# 02_PWR_IN.net
KiCad netlist of a schematic drawn in Altium Designer
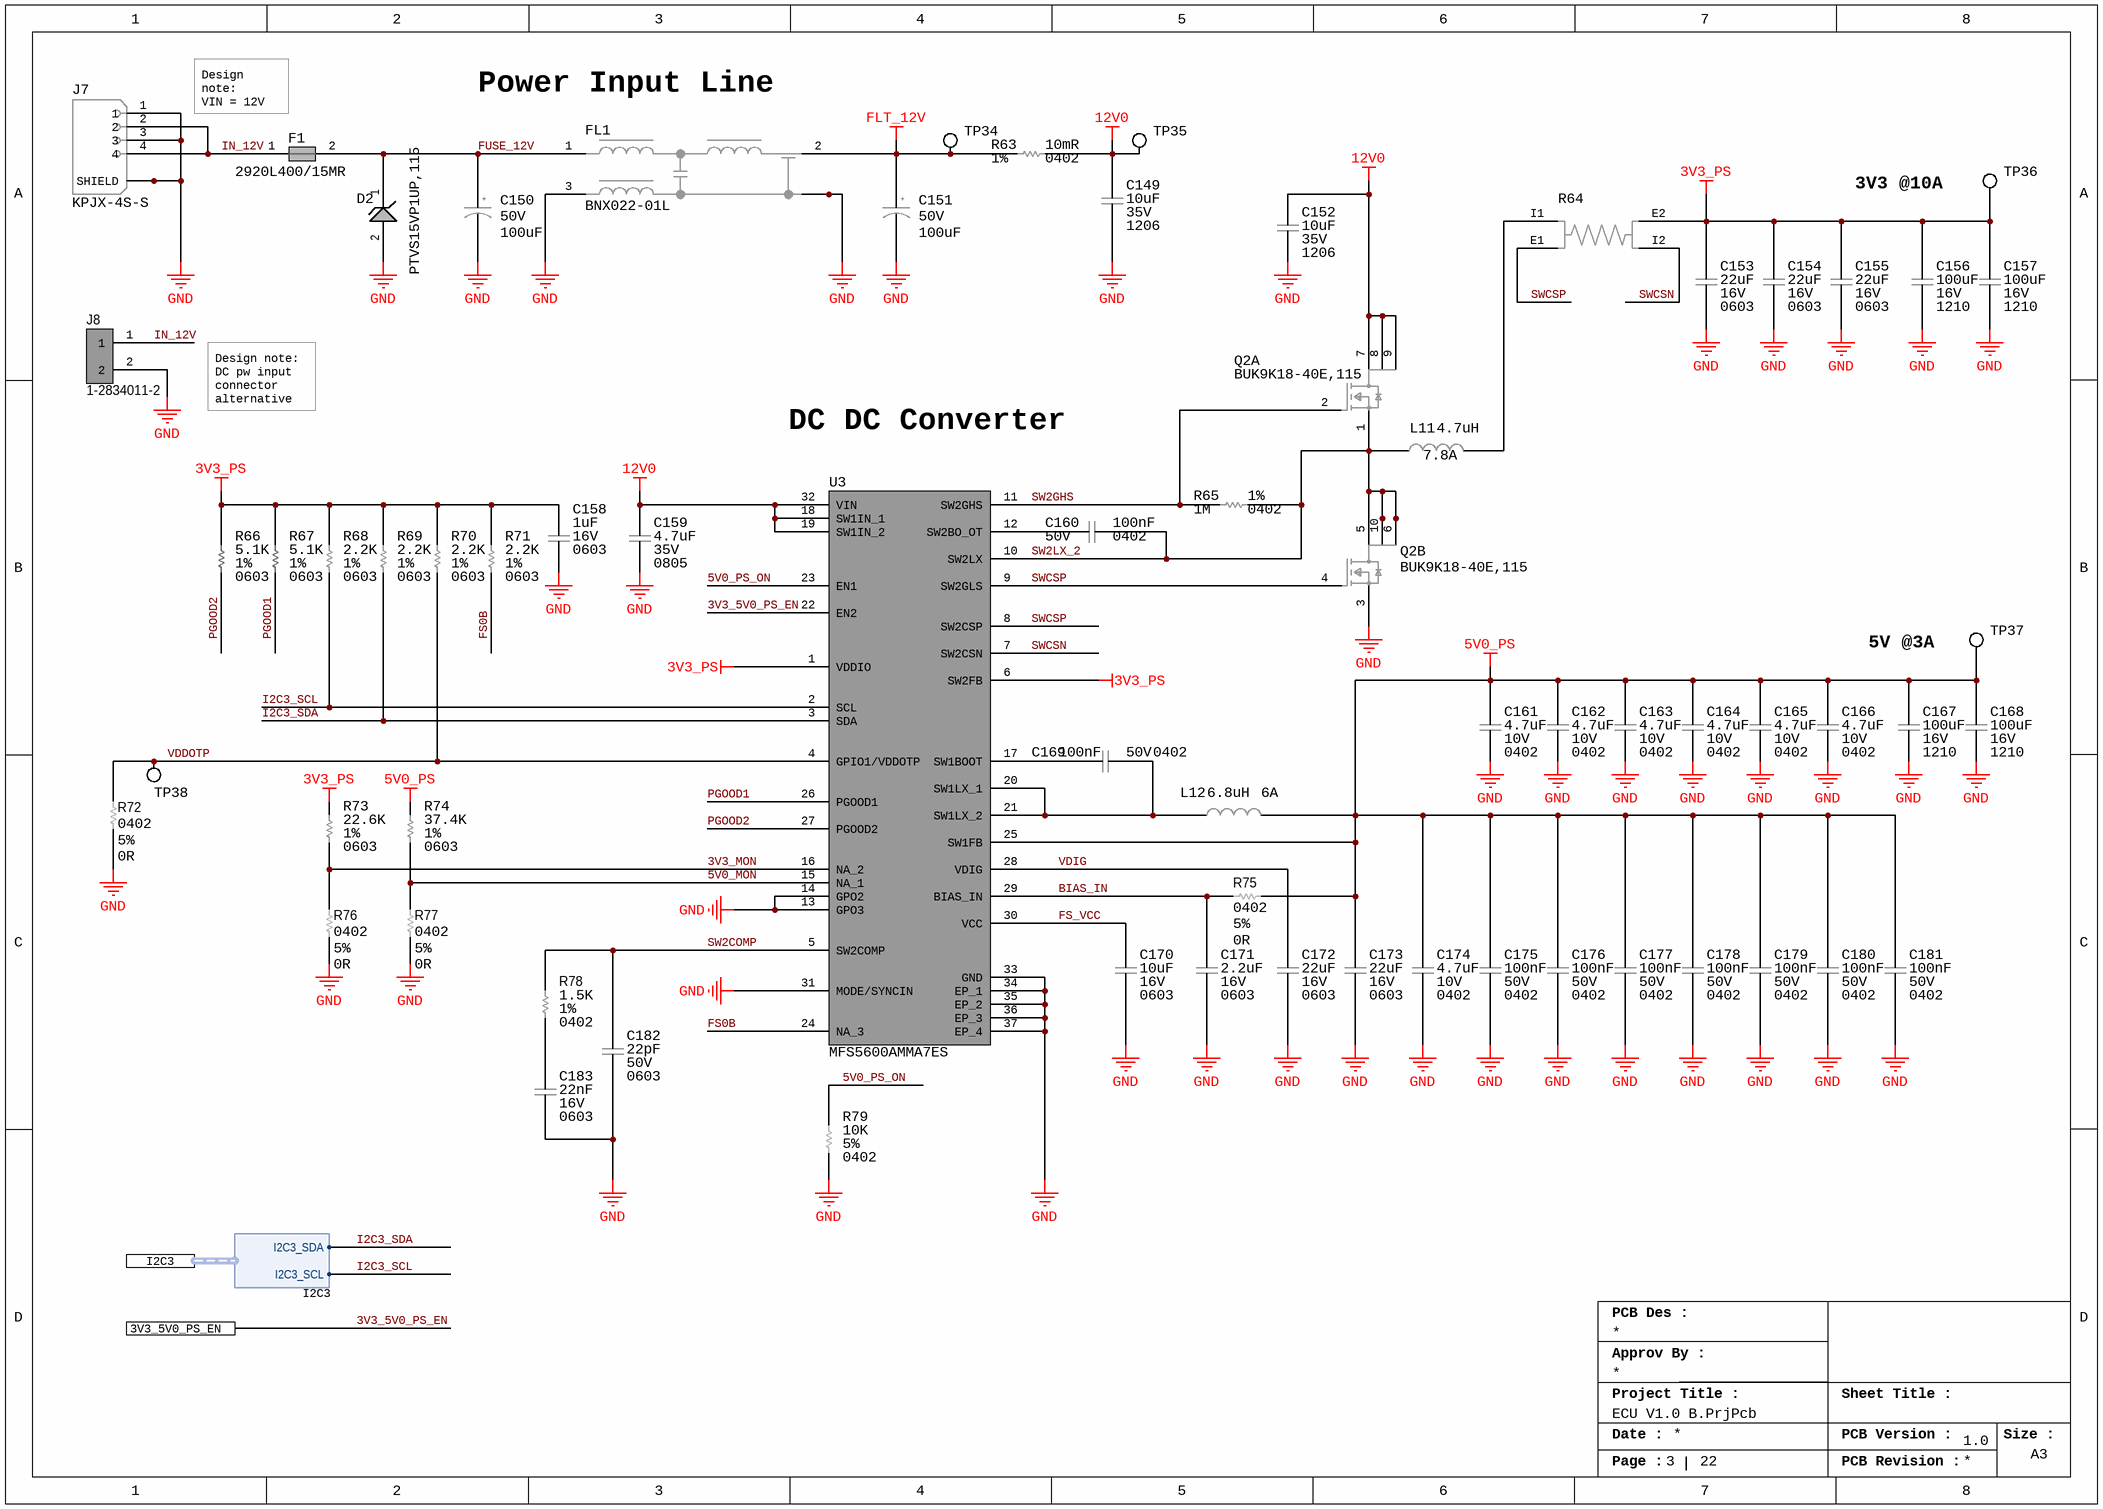
[diagram p0: 02_PWR IN.SchDoc]

(export (version "E")
  (design (tool "Eeschema 10.0.6"))
  (components
    (comp (ref "C149")
      (value "GRM319R6YA106KA12D")
      (footprint "CAP_1206_CAPC3216X16N")
      (description "1206 10 uF 35 V ±10 % Tolerance X5R SMT Multilayer Ceramic Capacitor")
      (fields
        (field (name "MANUFACTURER") "Murata")
        (field (name "TOLERANCE") "10%")
        (field (name "VOLTAGE RATING") "35V")
        (field (name "CAPACITANCE") "10uF")
        (field (name "CASE/PACKAGE") "1206")
      )
      (libsource (lib "Electronic Devices_LIB") (part "CAP_10uF_35V_X5R_1206"))
    )
    (comp (ref "C150")
      (value "UUD1H101MNL1GS")
      (footprint "CAP_POLA_UD(8X10)")
      (description "Radial Can - SMD ALUMINUM ELECTROLYTIC CAPACITOR UUD 50V 100muF ±20% 0.315Dia 8.00mm")
      (fields
        (field (name "MANUFACTURER") "Nichicon")
        (field (name "TOLERANCE") "20%")
        (field (name "VOLTAGE RATING (DC)") "50V")
        (field (name "CAPACITANCE") "100uF")
      )
      (libsource (lib "Electronic Devices_LIB") (part "CAP_100UF_50V_POL"))
    )
    (comp (ref "C151")
      (value "UUD1H101MNL1GS")
      (footprint "CAP_POLA_UD(8X10)")
      (description "Radial Can - SMD ALUMINUM ELECTROLYTIC CAPACITOR UUD 50V 100muF ±20% 0.315Dia 8.00mm")
      (fields
        (field (name "MANUFACTURER") "Nichicon")
        (field (name "TOLERANCE") "20%")
        (field (name "VOLTAGE RATING (DC)") "50V")
        (field (name "CAPACITANCE") "100uF")
      )
      (libsource (lib "Electronic Devices_LIB") (part "CAP_100UF_50V_POL"))
    )
    (comp (ref "C152")
      (value "GRM319R6YA106KA12D")
      (footprint "CAP_1206_CAPC3216X16N")
      (description "1206 10 uF 35 V ±10 % Tolerance X5R SMT Multilayer Ceramic Capacitor")
      (fields
        (field (name "MANUFACTURER") "Murata")
        (field (name "TOLERANCE") "10%")
        (field (name "VOLTAGE RATING") "35V")
        (field (name "CAPACITANCE") "10uF")
        (field (name "CASE/PACKAGE") "1206")
      )
      (libsource (lib "Electronic Devices_LIB") (part "CAP_10uF_35V_X5R_1206"))
    )
    (comp (ref "C153")
      (value "CL10A226MO7JZNC")
      (footprint "CAP_0603_CAPC1608X08N")
      (description "Cap Ceramic 22uF 16V X5R 20% Pad SMD 0603 85C T/R")
      (fields
        (field (name "MANUFACTURER") "Samsung")
        (field (name "TOLERANCE") "20%")
        (field (name "CAPACITANCE") "22uF")
        (field (name "VOLTAGE RATING") "16V")
        (field (name "CASE/PACKAGE") "0603")
      )
      (libsource (lib "Electronic Devices_LIB") (part "CAP_22UF_16V_X5R_0603"))
    )
    (comp (ref "C154")
      (value "CL10A226MO7JZNC")
      (footprint "CAP_0603_CAPC1608X08N")
      (description "Cap Ceramic 22uF 16V X5R 20% Pad SMD 0603 85C T/R")
      (fields
        (field (name "MANUFACTURER") "Samsung")
        (field (name "TOLERANCE") "20%")
        (field (name "CAPACITANCE") "22uF")
        (field (name "VOLTAGE RATING") "16V")
        (field (name "CASE/PACKAGE") "0603")
      )
      (libsource (lib "Electronic Devices_LIB") (part "CAP_22UF_16V_X5R_0603"))
    )
    (comp (ref "C155")
      (value "CL10A226MO7JZNC")
      (footprint "CAP_0603_CAPC1608X08N")
      (description "Cap Ceramic 22uF 16V X5R 20% Pad SMD 0603 85C T/R")
      (fields
        (field (name "MANUFACTURER") "Samsung")
        (field (name "TOLERANCE") "20%")
        (field (name "CAPACITANCE") "22uF")
        (field (name "VOLTAGE RATING") "16V")
        (field (name "CASE/PACKAGE") "0603")
      )
      (libsource (lib "Electronic Devices_LIB") (part "CAP_22UF_16V_X5R_0603"))
    )
    (comp (ref "C156")
      (value "EMK325ABJ107MM-T")
      (footprint "CAP_1210_CAPC3225X270N")
      (description "Multilayer Ceramic Capacitor, 100 uF, 16 V, ± 20%, X5R, 1210 [3225 Metric]")
      (fields
        (field (name "MANUFACTURER") "Taiyo Yuden")
        (field (name "TOLERANCE") "20%")
        (field (name "VOLTAGE RATING") "16V")
        (field (name "CAPACITANCE") "100uF")
        (field (name "CASE/PACKAGE") "1210")
      )
      (libsource (lib "Electronic Devices_LIB") (part "CAP_100UF_16V_X5R_1210"))
    )
    (comp (ref "C157")
      (value "EMK325ABJ107MM-T")
      (footprint "CAP_1210_CAPC3225X270N")
      (description "Multilayer Ceramic Capacitor, 100 uF, 16 V, ± 20%, X5R, 1210 [3225 Metric]")
      (fields
        (field (name "MANUFACTURER") "Taiyo Yuden")
        (field (name "TOLERANCE") "20%")
        (field (name "VOLTAGE RATING") "16V")
        (field (name "CAPACITANCE") "100uF")
        (field (name "CASE/PACKAGE") "1210")
      )
      (libsource (lib "Electronic Devices_LIB") (part "CAP_100UF_16V_X5R_1210"))
    )
    (comp (ref "C158")
      (value "CL10A105KO8NNNC")
      (footprint "CAP_0603_CAPC1608X08N")
      (description "CAP CER 1UF 16V X5R 0603")
      (fields
        (field (name "MANUFACTURER") "Samsung")
        (field (name "TOLERANCE") "10%")
        (field (name "VOLTAGE RATING") "16V")
        (field (name "CAPACITANCE") "1uF")
        (field (name "CASE/PACKAGE") "0603")
      )
      (libsource (lib "Electronic Devices_LIB") (part "CAP_1UF_16V_X5R_0603"))
    )
    (comp (ref "C159")
      (value "CL21A475KLCLQNC")
      (footprint "CAP_0805_CAPC2012X12N")
      (description "CL Series 0805 35 V 4.7 uF ±10% Tolerance X5R Multilayer Ceramic Chip Capacitor")
      (fields
        (field (name "MANUFACTURER") "Samsung")
        (field (name "TOLERANCE") "10%")
        (field (name "VOLTAGE RATING") "35V")
        (field (name "CAPACITANCE") "4.7uF")
        (field (name "CASE/PACKAGE") "0805")
      )
      (libsource (lib "Electronic Devices_LIB") (part "CAP_4.7uF_35V_X5R_0805"))
    )
    (comp (ref "C160")
      (value "GRM155R71H104KE14D")
      (footprint "CAP_0402_CAPC1005X05N")
      (description "Multilayer Ceramic Capacitor, 0.1 uF, 16 V, ± 10%, X7R, 0402 [1005 Metric]")
      (fields
        (field (name "MANUFACTURER") "Murata")
        (field (name "TOLERANCE") "10%")
        (field (name "VOLTAGE RATING") "50V")
        (field (name "CAPACITANCE") "100nF")
        (field (name "CASE/PACKAGE") "0402")
      )
      (libsource (lib "Electronic Devices_LIB") (part "CAP_100NF_50V_X7R_0402"))
    )
    (comp (ref "C161")
      (value "CL05A475KP5NRNC")
      (footprint "CAP_0402_CAPC1005X05N")
      (description "Multilayer Ceramic Capacitor, 4.7 uF, 10 V, ± 10%, X5R, 0402 [1005 Metric]")
      (fields
        (field (name "MANUFACTURER") "Samsung")
        (field (name "TOLERANCE") "10%")
        (field (name "CAPACITANCE") "4.7uF")
        (field (name "VOLTAGE RATING") "10V")
        (field (name "CASE/PACKAGE") "0402")
      )
      (libsource (lib "Electronic Devices_LIB") (part "CAP_4.7UF_10V_X5R_0402"))
    )
    (comp (ref "C162")
      (value "CL05A475KP5NRNC")
      (footprint "CAP_0402_CAPC1005X05N")
      (description "Multilayer Ceramic Capacitor, 4.7 uF, 10 V, ± 10%, X5R, 0402 [1005 Metric]")
      (fields
        (field (name "MANUFACTURER") "Samsung")
        (field (name "TOLERANCE") "10%")
        (field (name "CAPACITANCE") "4.7uF")
        (field (name "VOLTAGE RATING") "10V")
        (field (name "CASE/PACKAGE") "0402")
      )
      (libsource (lib "Electronic Devices_LIB") (part "CAP_4.7UF_10V_X5R_0402"))
    )
    (comp (ref "C163")
      (value "CL05A475KP5NRNC")
      (footprint "CAP_0402_CAPC1005X05N")
      (description "Multilayer Ceramic Capacitor, 4.7 uF, 10 V, ± 10%, X5R, 0402 [1005 Metric]")
      (fields
        (field (name "MANUFACTURER") "Samsung")
        (field (name "TOLERANCE") "10%")
        (field (name "CAPACITANCE") "4.7uF")
        (field (name "VOLTAGE RATING") "10V")
        (field (name "CASE/PACKAGE") "0402")
      )
      (libsource (lib "Electronic Devices_LIB") (part "CAP_4.7UF_10V_X5R_0402"))
    )
    (comp (ref "C164")
      (value "CL05A475KP5NRNC")
      (footprint "CAP_0402_CAPC1005X05N")
      (description "Multilayer Ceramic Capacitor, 4.7 uF, 10 V, ± 10%, X5R, 0402 [1005 Metric]")
      (fields
        (field (name "MANUFACTURER") "Samsung")
        (field (name "TOLERANCE") "10%")
        (field (name "CAPACITANCE") "4.7uF")
        (field (name "VOLTAGE RATING") "10V")
        (field (name "CASE/PACKAGE") "0402")
      )
      (libsource (lib "Electronic Devices_LIB") (part "CAP_4.7UF_10V_X5R_0402"))
    )
    (comp (ref "C165")
      (value "CL05A475KP5NRNC")
      (footprint "CAP_0402_CAPC1005X05N")
      (description "Multilayer Ceramic Capacitor, 4.7 uF, 10 V, ± 10%, X5R, 0402 [1005 Metric]")
      (fields
        (field (name "MANUFACTURER") "Samsung")
        (field (name "TOLERANCE") "10%")
        (field (name "CAPACITANCE") "4.7uF")
        (field (name "VOLTAGE RATING") "10V")
        (field (name "CASE/PACKAGE") "0402")
      )
      (libsource (lib "Electronic Devices_LIB") (part "CAP_4.7UF_10V_X5R_0402"))
    )
    (comp (ref "C166")
      (value "CL05A475KP5NRNC")
      (footprint "CAP_0402_CAPC1005X05N")
      (description "Multilayer Ceramic Capacitor, 4.7 uF, 10 V, ± 10%, X5R, 0402 [1005 Metric]")
      (fields
        (field (name "MANUFACTURER") "Samsung")
        (field (name "TOLERANCE") "10%")
        (field (name "CAPACITANCE") "4.7uF")
        (field (name "VOLTAGE RATING") "10V")
        (field (name "CASE/PACKAGE") "0402")
      )
      (libsource (lib "Electronic Devices_LIB") (part "CAP_4.7UF_10V_X5R_0402"))
    )
    (comp (ref "C167")
      (value "EMK325ABJ107MM-T")
      (footprint "CAP_1210_CAPC3225X270N")
      (description "Multilayer Ceramic Capacitor, 100 uF, 16 V, ± 20%, X5R, 1210 [3225 Metric]")
      (fields
        (field (name "MANUFACTURER") "Taiyo Yuden")
        (field (name "TOLERANCE") "20%")
        (field (name "VOLTAGE RATING") "16V")
        (field (name "CAPACITANCE") "100uF")
        (field (name "CASE/PACKAGE") "1210")
      )
      (libsource (lib "Electronic Devices_LIB") (part "CAP_100UF_16V_X5R_1210"))
    )
    (comp (ref "C168")
      (value "EMK325ABJ107MM-T")
      (footprint "CAP_1210_CAPC3225X270N")
      (description "Multilayer Ceramic Capacitor, 100 uF, 16 V, ± 20%, X5R, 1210 [3225 Metric]")
      (fields
        (field (name "MANUFACTURER") "Taiyo Yuden")
        (field (name "TOLERANCE") "20%")
        (field (name "VOLTAGE RATING") "16V")
        (field (name "CAPACITANCE") "100uF")
        (field (name "CASE/PACKAGE") "1210")
      )
      (libsource (lib "Electronic Devices_LIB") (part "CAP_100UF_16V_X5R_1210"))
    )
    (comp (ref "C169")
      (value "GRM155R71H104KE14D")
      (footprint "CAP_0402_CAPC1005X05N")
      (description "Multilayer Ceramic Capacitor, 0.1 uF, 16 V, ± 10%, X7R, 0402 [1005 Metric]")
      (fields
        (field (name "MANUFACTURER") "Murata")
        (field (name "TOLERANCE") "10%")
        (field (name "VOLTAGE RATING") "50V")
        (field (name "CAPACITANCE") "100nF")
        (field (name "CASE/PACKAGE") "0402")
      )
      (libsource (lib "Electronic Devices_LIB") (part "CAP_100NF_50V_X7R_0402"))
    )
    (comp (ref "C170")
      (value "GRM188R61C106MAALD")
      (footprint "CAP_0603_CAPC1608X08N")
      (description "0603 10 uF 16 V ±20% Tolerance X5R Multilayer Ceramic Chip Capacitor")
      (fields
        (field (name "MANUFACTURER") "Murata")
        (field (name "TOLERANCE") "20%")
        (field (name "VOLTAGE RATING") "16V")
        (field (name "CAPACITANCE") "10uF")
        (field (name "CASE/PACKAGE") "0603")
      )
      (libsource (lib "Electronic Devices_LIB") (part "CAP_10UF_16V_X5R_0603"))
    )
    (comp (ref "C171")
      (value "EMK107BB7225KA-T")
      (footprint "CAP_0603_CAPC1608X08N")
      (description "Multilayer Ceramic Capacitors (High dielectric type), 16V, 2.2 uF, ± 10 %, 0603, X7R, RoHS")
      (fields
        (field (name "MANUFACTURER") "Taiyo Yuden")
        (field (name "TOLERANCE") "10%")
        (field (name "CASE/PACKAGE") "0603")
        (field (name "CAPACITANCE") "2.2uF")
        (field (name "VOLTAGE RATING") "16V")
      )
      (libsource (lib "Electronic Devices_LIB") (part "CAP_2.2UF_16V_X7R_0603"))
    )
    (comp (ref "C172")
      (value "CL10A226MO7JZNC")
      (footprint "CAP_0603_CAPC1608X08N")
      (description "Cap Ceramic 22uF 16V X5R 20% Pad SMD 0603 85C T/R")
      (fields
        (field (name "MANUFACTURER") "Samsung")
        (field (name "TOLERANCE") "20%")
        (field (name "CAPACITANCE") "22uF")
        (field (name "VOLTAGE RATING") "16V")
        (field (name "CASE/PACKAGE") "0603")
      )
      (libsource (lib "Electronic Devices_LIB") (part "CAP_22UF_16V_X5R_0603"))
    )
    (comp (ref "C173")
      (value "CL10A226MO7JZNC")
      (footprint "CAP_0603_CAPC1608X08N")
      (description "Cap Ceramic 22uF 16V X5R 20% Pad SMD 0603 85C T/R")
      (fields
        (field (name "MANUFACTURER") "Samsung")
        (field (name "TOLERANCE") "20%")
        (field (name "CAPACITANCE") "22uF")
        (field (name "VOLTAGE RATING") "16V")
        (field (name "CASE/PACKAGE") "0603")
      )
      (libsource (lib "Electronic Devices_LIB") (part "CAP_22UF_16V_X5R_0603"))
    )
    (comp (ref "C174")
      (value "CL05A475KP5NRNC")
      (footprint "CAP_0402_CAPC1005X05N")
      (description "Multilayer Ceramic Capacitor, 4.7 uF, 10 V, ± 10%, X5R, 0402 [1005 Metric]")
      (fields
        (field (name "MANUFACTURER") "Samsung")
        (field (name "TOLERANCE") "10%")
        (field (name "CAPACITANCE") "4.7uF")
        (field (name "VOLTAGE RATING") "10V")
        (field (name "CASE/PACKAGE") "0402")
      )
      (libsource (lib "Electronic Devices_LIB") (part "CAP_4.7UF_10V_X5R_0402"))
    )
    (comp (ref "C175")
      (value "GRM155R71H104KE14D")
      (footprint "CAP_0402_CAPC1005X05N")
      (description "Multilayer Ceramic Capacitor, 0.1 uF, 16 V, ± 10%, X7R, 0402 [1005 Metric]")
      (fields
        (field (name "MANUFACTURER") "Murata")
        (field (name "TOLERANCE") "10%")
        (field (name "VOLTAGE RATING") "50V")
        (field (name "CAPACITANCE") "100nF")
        (field (name "CASE/PACKAGE") "0402")
      )
      (libsource (lib "Electronic Devices_LIB") (part "CAP_100NF_50V_X7R_0402"))
    )
    (comp (ref "C176")
      (value "GRM155R71H104KE14D")
      (footprint "CAP_0402_CAPC1005X05N")
      (description "Multilayer Ceramic Capacitor, 0.1 uF, 16 V, ± 10%, X7R, 0402 [1005 Metric]")
      (fields
        (field (name "MANUFACTURER") "Murata")
        (field (name "TOLERANCE") "10%")
        (field (name "VOLTAGE RATING") "50V")
        (field (name "CAPACITANCE") "100nF")
        (field (name "CASE/PACKAGE") "0402")
      )
      (libsource (lib "Electronic Devices_LIB") (part "CAP_100NF_50V_X7R_0402"))
    )
    (comp (ref "C177")
      (value "GRM155R71H104KE14D")
      (footprint "CAP_0402_CAPC1005X05N")
      (description "Multilayer Ceramic Capacitor, 0.1 uF, 16 V, ± 10%, X7R, 0402 [1005 Metric]")
      (fields
        (field (name "MANUFACTURER") "Murata")
        (field (name "TOLERANCE") "10%")
        (field (name "VOLTAGE RATING") "50V")
        (field (name "CAPACITANCE") "100nF")
        (field (name "CASE/PACKAGE") "0402")
      )
      (libsource (lib "Electronic Devices_LIB") (part "CAP_100NF_50V_X7R_0402"))
    )
    (comp (ref "C178")
      (value "GRM155R71H104KE14D")
      (footprint "CAP_0402_CAPC1005X05N")
      (description "Multilayer Ceramic Capacitor, 0.1 uF, 16 V, ± 10%, X7R, 0402 [1005 Metric]")
      (fields
        (field (name "MANUFACTURER") "Murata")
        (field (name "TOLERANCE") "10%")
        (field (name "VOLTAGE RATING") "50V")
        (field (name "CAPACITANCE") "100nF")
        (field (name "CASE/PACKAGE") "0402")
      )
      (libsource (lib "Electronic Devices_LIB") (part "CAP_100NF_50V_X7R_0402"))
    )
    (comp (ref "C179")
      (value "GRM155R71H104KE14D")
      (footprint "CAP_0402_CAPC1005X05N")
      (description "Multilayer Ceramic Capacitor, 0.1 uF, 16 V, ± 10%, X7R, 0402 [1005 Metric]")
      (fields
        (field (name "MANUFACTURER") "Murata")
        (field (name "TOLERANCE") "10%")
        (field (name "VOLTAGE RATING") "50V")
        (field (name "CAPACITANCE") "100nF")
        (field (name "CASE/PACKAGE") "0402")
      )
      (libsource (lib "Electronic Devices_LIB") (part "CAP_100NF_50V_X7R_0402"))
    )
    (comp (ref "C180")
      (value "GRM155R71H104KE14D")
      (footprint "CAP_0402_CAPC1005X05N")
      (description "Multilayer Ceramic Capacitor, 0.1 uF, 16 V, ± 10%, X7R, 0402 [1005 Metric]")
      (fields
        (field (name "MANUFACTURER") "Murata")
        (field (name "TOLERANCE") "10%")
        (field (name "VOLTAGE RATING") "50V")
        (field (name "CAPACITANCE") "100nF")
        (field (name "CASE/PACKAGE") "0402")
      )
      (libsource (lib "Electronic Devices_LIB") (part "CAP_100NF_50V_X7R_0402"))
    )
    (comp (ref "C181")
      (value "GRM155R71H104KE14D")
      (footprint "CAP_0402_CAPC1005X05N")
      (description "Multilayer Ceramic Capacitor, 0.1 uF, 16 V, ± 10%, X7R, 0402 [1005 Metric]")
      (fields
        (field (name "MANUFACTURER") "Murata")
        (field (name "TOLERANCE") "10%")
        (field (name "VOLTAGE RATING") "50V")
        (field (name "CAPACITANCE") "100nF")
        (field (name "CASE/PACKAGE") "0402")
      )
      (libsource (lib "Electronic Devices_LIB") (part "CAP_100NF_50V_X7R_0402"))
    )
    (comp (ref "C182")
      (value "C0603C220J5GACTU")
      (footprint "CAP_0603_CAPC1608X08N")
      (description "Multilayer Ceramic Capacitor, 22 pF, 50 V, ï¿½ 5%, C0G (NP0), 0603 [1608 Metric]")
      (fields
        (field (name "MANUFACTURER") "KEMET")
        (field (name "TOLERANCE") "5%")
        (field (name "VOLTAGE RATING (DC)") "50V")
        (field (name "CAPACITANCE") "22pF")
        (field (name "CASE/PACKAGE") "0603")
      )
      (libsource (lib "Electronic Devices_LIB") (part "CAP_22pF_50V_NP0_0603"))
    )
    (comp (ref "C183")
      (value "C0603C223K4RACTU")
      (footprint "CAP_0603_CAPC1608X08N")
      (description "Multilayer Ceramic Capacitor, 0.022 uF, 16 V, ± 10%, X7R, 0603 [1608 Metric]")
      (fields
        (field (name "MANUFACTURER") "KEMET")
        (field (name "TOLERANCE") "10%")
        (field (name "VOLTAGE RATING (DC)") "16V")
        (field (name "CAPACITANCE") "22nF")
        (field (name "CASE/PACKAGE") "0603")
      )
      (libsource (lib "Electronic Devices_LIB") (part "CAP_22nF_16V_X7R_0603"))
    )
    (comp (ref "D2")
      (value "PTVS15VP1UP,115")
      (footprint "PMEG3050EP115")
      (description "TVS DIODE 15VWM 24.4VC SOD128")
      (fields (field (name "MANUFACTURER") "Nexperia"))
      (libsource (lib "Electronic Devices_LIB") (part "DIO_TVS_24.4V_PTVS15VP1UP,115"))
    )
    (comp (ref "F1")
      (value "2920L400/15MR")
      (footprint "2920L07560MR")
      (description "PTC Resettable Fuse 4A(hold) 8A(trip) 15VDC 40A 1.5W 4s 0.01Ohm SMD Solder Pad 2920 T/R")
      (fields (field (name "MANUFACTURER") "Littelfuse"))
      (libsource (lib "Electronic Devices_LIB") (part "FUSE_PTC_8A_2920L400/15MR"))
    )
    (comp (ref "FL1")
      (value "BNX022-01L")
      (footprint "FILTER_BNX022-01L")
      (description "EMI Filter 1MHz to 1000MHz 35dB 10A 50VDC Flat Style SMD Embossed T/R")
      (fields (field (name "MANUFACTURER") "Murata"))
      (libsource (lib "Electronic Devices_LIB") (part "FILTER_EMI_50VDC_10A_BNX022-01L"))
    )
    (comp (ref "J7")
      (value "KPJX-4S-S")
      (footprint "CONN_DC_KYCON_KPJX-4S-S")
      (description "Conn Power SKT 4 POS Solder ST Thru-Hole 4 Terminal 1 Port")
      (fields (field (name "MANUFACTURER") "Kycon"))
      (libsource (lib "Electronic Devices_LIB") (part "CONN_DC_JACK_PWR_KPJX-4S-S"))
    )
    (comp (ref "J8")
      (value "1-2834011-2")
      (footprint "CONN_TBLOCK_128340112")
      (description "2POS3.5MMTOPENTRYSCREWLESSC")
      (fields (field (name "MANUFACTURER") "TE Connectivity") (field (name "VOLTAGE") "300V"))
      (libsource (lib "Electronic Devices_LIB") (part "CONN_TBLOCK_2P_3.5mm_1-2834011-2"))
    )
    (comp (ref "L11")
      (value "SPM7054VT-4R7M-D")
      (footprint "SPM7054VT")
      (description "Inductor Power Shielded Wirewound 4.7uH 20% 100KHz Metal 7.8A 0.01826Ohm DCR Automotive T/R")
      (fields
        (field (name "MANUFACTURER") "TDK")
        (field (name "CURRENT RATING") "7.8A")
        (field (name "INDUCTANCE") "4.7uH")
      )
      (libsource (lib "Electronic Devices_LIB") (part "IND_4.7uH_7.8A_SPM7054VT-4R7M-D"))
    )
    (comp (ref "L12")
      (value "74437368068")
      (footprint "WE-LHMI_104048")
      (description "WE-LHMI; 6800 nH; Composite Iron Multilayer SMD Inductor; 1040 Case; .013GHz 6A")
      (fields
        (field (name "MANUFACTURER") "Wurth Electronics")
        (field (name "TOLERANCE") "20%")
        (field (name "MAX DC CURRENT") "6A")
        (field (name "INDUCTANCE") "6.8uH")
      )
      (libsource (lib "Electronic Devices_LIB") (part "IND_6.8uH_6A_74437368068"))
    )
    (comp (ref "Q2")
      (value "BUK9K18-40E,115")
      (footprint "BUK9K1840E115")
      (description "Transistor MOSFET Array Dual N -CH 40V 30A 8-Pin LFPAK-56D T/R")
      (fields (field (name "MANUFACTURER") "Nexperia"))
      (libsource (lib "Electronic Devices_LIB") (part "TRANS_FET_CH__N_40V_30A_BUK9K18-40E,115"))
    )
    (comp (ref "R63")
      (value "ERJ-2LWFR010X")
      (footprint "RES_0603_RESC1608X04N")
      (description "Res Current Sense Thick Film 0402 0.01 Ohm 1% 1/5W 0ppm/°C to 500ppm/°C Molded T/R")
      (fields
        (field (name "MANUFACTURER") "Panasonic")
        (field (name "TOLERANCE") "1%")
        (field (name "RESISTANCE") "10mR")
        (field (name "CASE/PACKAGE") "0402")
      )
      (libsource (lib "Electronic Devices_LIB") (part "RES_10mR_1%_0.05W_0402"))
    )
    (comp (ref "R64")
      (value "WSK2512R0100FEA")
      (footprint "RES_WSK2512R0100FEA")
      (description "Fixed Resistor, Metal Strip, 1W, 0.01ohm, 0.1V, 1% +/-Tol, 35ppm/Cel, Surface Mount, 2512")
      (fields (field (name "MANUFACTURER") "Vishay") (field (name "TOLERANCE") "1%"))
      (libsource (lib "Electronic Devices_LIB") (part "RES_10mR_1%_1W_2512"))
    )
    (comp (ref "R65")
      (value "CR0402-FX-1004GLF")
      (footprint "RES_0402_RESC1005X04N")
      (description "Res Thick Film 0402 1M Ohm 1% 1/16W ±100ppm/°C Molded SMD SMD Paper Tape on Plastic Reel")
      (fields
        (field (name "MANUFACTURER") "Bourns")
        (field (name "RESISTANCE") "1M")
        (field (name "TOLERANCE") "1%")
        (field (name "CASE/PACKAGE") "0402")
      )
      (libsource (lib "Electronic Devices_LIB") (part "RES_1M_1%_63mW_0402"))
    )
    (comp (ref "R66")
      (value "RC0603FR-075K1L")
      (footprint "RES_0603_RESC1608X04N")
      (description "SMD Chip Resistor, 5.1 kOhm, ± 1%, 100 mW, 0603 [1608 Metric], Thick Film, General Purpose")
      (fields
        (field (name "MANUFACTURER") "Yageo")
        (field (name "TOLERANCE") "1%")
        (field (name "RESISTANCE") "5.1K")
        (field (name "CASE/PACKAGE") "0603")
      )
      (libsource (lib "Electronic Devices_LIB") (part "RES_5.1K_1%_100mW_0603"))
    )
    (comp (ref "R67")
      (value "RC0603FR-075K1L")
      (footprint "RES_0603_RESC1608X04N")
      (description "SMD Chip Resistor, 5.1 kOhm, ± 1%, 100 mW, 0603 [1608 Metric], Thick Film, General Purpose")
      (fields
        (field (name "MANUFACTURER") "Yageo")
        (field (name "TOLERANCE") "1%")
        (field (name "RESISTANCE") "5.1K")
        (field (name "CASE/PACKAGE") "0603")
      )
      (libsource (lib "Electronic Devices_LIB") (part "RES_5.1K_1%_100mW_0603"))
    )
    (comp (ref "R68")
      (value "RC0603FR-072K2L")
      (footprint "RES_0603_RESC1608X04N")
      (description "SMD Chip Resistor, 2.2 Kohm, ½ 1%, 100 Mw, 0603 [1608 Metric], Thick Film, General Purpose")
      (fields
        (field (name "MANUFACTURER") "Yageo")
        (field (name "TOLERANCE") "1%")
        (field (name "RESISTANCE") "2.2K")
        (field (name "CASE/PACKAGE") "0603")
      )
      (libsource (lib "Electronic Devices_LIB") (part "RES_2.2K_1%_100mW_0603"))
    )
    (comp (ref "R69")
      (value "RC0603FR-072K2L")
      (footprint "RES_0603_RESC1608X04N")
      (description "SMD Chip Resistor, 2.2 Kohm, ½ 1%, 100 Mw, 0603 [1608 Metric], Thick Film, General Purpose")
      (fields
        (field (name "MANUFACTURER") "Yageo")
        (field (name "TOLERANCE") "1%")
        (field (name "RESISTANCE") "2.2K")
        (field (name "CASE/PACKAGE") "0603")
      )
      (libsource (lib "Electronic Devices_LIB") (part "RES_2.2K_1%_100mW_0603"))
    )
    (comp (ref "R70")
      (value "RC0603FR-072K2L")
      (footprint "RES_0603_RESC1608X04N")
      (description "SMD Chip Resistor, 2.2 Kohm, ½ 1%, 100 Mw, 0603 [1608 Metric], Thick Film, General Purpose")
      (fields
        (field (name "MANUFACTURER") "Yageo")
        (field (name "TOLERANCE") "1%")
        (field (name "RESISTANCE") "2.2K")
        (field (name "CASE/PACKAGE") "0603")
      )
      (libsource (lib "Electronic Devices_LIB") (part "RES_2.2K_1%_100mW_0603"))
    )
    (comp (ref "R71")
      (value "RC0603FR-072K2L")
      (footprint "RES_0603_RESC1608X04N")
      (description "SMD Chip Resistor, 2.2 Kohm, ½ 1%, 100 Mw, 0603 [1608 Metric], Thick Film, General Purpose")
      (fields
        (field (name "MANUFACTURER") "Yageo")
        (field (name "TOLERANCE") "1%")
        (field (name "RESISTANCE") "2.2K")
        (field (name "CASE/PACKAGE") "0603")
      )
      (libsource (lib "Electronic Devices_LIB") (part "RES_2.2K_1%_100mW_0603"))
    )
    (comp (ref "R72")
      (value "ERJ-2GE0R00X")
      (footprint "RES_0402_RESC1005X04N")
      (description "SMD Chip Resistor, Jumper, 0 ohm, 100 mW, 0402 [1005 Metric], Thick Film, General Purpose")
      (fields
        (field (name "MANUFACTURER") "Panasonic")
        (field (name "CASE CODE (IMPERIAL)") "0402")
        (field (name "TOLERANCE") "5%")
        (field (name "RESISTANCE") "0R")
      )
      (libsource (lib "Electronic Devices_LIB") (part "RES_0R_5%_100mW_0402"))
    )
    (comp (ref "R73")
      (value "AC0603FR-0722K6L")
      (footprint "RES_0603_RESC1608X04N")
      (description "Res Thick Film 0603 22.6K Ohm 1% 0.1W(1/10W) ±100ppm/C Pad SMD Automotive T/R")
      (fields
        (field (name "MANUFACTURER") "Yageo")
        (field (name "TOLERANCE") "1%")
        (field (name "RESISTANCE") "22.6K")
        (field (name "CASE/PACKAGE") "0603")
      )
      (libsource (lib "Electronic Devices_LIB") (part "RES_22.6K_1%_100mW_0603"))
    )
    (comp (ref "R74")
      (value "RC0603FR-0737K4L")
      (footprint "RES_0603_RESC1608X04N")
      (description "SMD Chip Resistor, 37.4 kOhm, ± 1%, 100 mW, 0603 [1608 Metric], Thick Film, General Purpose")
      (fields
        (field (name "MANUFACTURER") "Yageo")
        (field (name "TOLERANCE") "1%")
        (field (name "RESISTANCE") "37.4K")
        (field (name "CASE/PACKAGE") "0603")
      )
      (libsource (lib "Electronic Devices_LIB") (part "RES_37.4K_1%_100mW_0603"))
    )
    (comp (ref "R75")
      (value "ERJ-2GE0R00X")
      (footprint "RES_0402_RESC1005X04N")
      (description "SMD Chip Resistor, Jumper, 0 ohm, 100 mW, 0402 [1005 Metric], Thick Film, General Purpose")
      (fields
        (field (name "MANUFACTURER") "Panasonic")
        (field (name "CASE CODE (IMPERIAL)") "0402")
        (field (name "TOLERANCE") "5%")
        (field (name "RESISTANCE") "0R")
      )
      (libsource (lib "Electronic Devices_LIB") (part "RES_0R_5%_100mW_0402"))
    )
    (comp (ref "R76")
      (value "ERJ-2GE0R00X")
      (footprint "RES_0402_RESC1005X04N")
      (description "SMD Chip Resistor, Jumper, 0 ohm, 100 mW, 0402 [1005 Metric], Thick Film, General Purpose")
      (fields
        (field (name "MANUFACTURER") "Panasonic")
        (field (name "CASE CODE (IMPERIAL)") "0402")
        (field (name "TOLERANCE") "5%")
        (field (name "RESISTANCE") "0R")
      )
      (libsource (lib "Electronic Devices_LIB") (part "RES_0R_5%_100mW_0402"))
    )
    (comp (ref "R77")
      (value "ERJ-2GE0R00X")
      (footprint "RES_0402_RESC1005X04N")
      (description "SMD Chip Resistor, Jumper, 0 ohm, 100 mW, 0402 [1005 Metric], Thick Film, General Purpose")
      (fields
        (field (name "MANUFACTURER") "Panasonic")
        (field (name "CASE CODE (IMPERIAL)") "0402")
        (field (name "TOLERANCE") "5%")
        (field (name "RESISTANCE") "0R")
      )
      (libsource (lib "Electronic Devices_LIB") (part "RES_0R_5%_100mW_0402"))
    )
    (comp (ref "R78")
      (value "CR0402-FX-1501GLF")
      (footprint "RES_0402_RESC1005X04N")
      (description "Res Thick Film 0402 1.5K Ohm 1% 1/16W ±100ppm/°C Molded SMD SMD Paper Tape on Plastic Reel")
      (fields
        (field (name "MANUFACTURER") "Bourns")
        (field (name "RESISTANCE") "1.5K")
        (field (name "TOLERANCE") "1%")
        (field (name "CASE/PACKAGE") "0402")
      )
      (libsource (lib "Electronic Devices_LIB") (part "RES_1.5K_1%_63mW_0402"))
    )
    (comp (ref "R79")
      (value "ERJ-2GEJ103X")
      (footprint "RES_0402_RESC1005X04N")
      (description "Res Thick Film 0402 10K Ohm 5% 1/10W ±200ppm/°C Molded SMD Punched Carrier T/R")
      (fields
        (field (name "MANUFACTURER") "Panasonic")
        (field (name "TOLERANCE") "5%")
        (field (name "RESISTANCE") "10K")
        (field (name "CASE/PACKAGE") "0402")
      )
      (libsource (lib "Electronic Devices_LIB") (part "RES_10K_5%_100mW_0402"))
    )
    (comp (ref "TP34")
      (value "NO COMPONENT")
      (footprint "TP_PAD_0.5MM_SMD_ROUND")
      (description "Test Point, SMD pad, round, 1.5mm, 1.6mm, 3mm diameter")
      (libsource (lib "Electronic Devices_LIB") (part "TP_PAD_SMD_SMALL"))
    )
    (comp (ref "TP35")
      (value "NO COMPONENT")
      (footprint "TP_PAD_0.5MM_SMD_ROUND")
      (description "Test Point, SMD pad, round, 1.5mm, 1.6mm, 3mm diameter")
      (libsource (lib "Electronic Devices_LIB") (part "TP_PAD_SMD_SMALL"))
    )
    (comp (ref "TP36")
      (value "NO COMPONENT")
      (footprint "TP_PAD_0.5MM_SMD_ROUND")
      (description "Test Point, SMD pad, round, 1.5mm, 1.6mm, 3mm diameter")
      (libsource (lib "Electronic Devices_LIB") (part "TP_PAD_SMD_SMALL"))
    )
    (comp (ref "TP37")
      (value "NO COMPONENT")
      (footprint "TP_PAD_0.5MM_SMD_ROUND")
      (description "Test Point, SMD pad, round, 1.5mm, 1.6mm, 3mm diameter")
      (libsource (lib "Electronic Devices_LIB") (part "TP_PAD_SMD_SMALL"))
    )
    (comp (ref "TP38")
      (value "NO COMPONENT")
      (footprint "TP_PAD_0.5MM_SMD_ROUND")
      (description "Test Point, SMD pad, round, 1.5mm, 1.6mm, 3mm diameter")
      (libsource (lib "Electronic Devices_LIB") (part "TP_PAD_SMD_SMALL"))
    )
    (comp (ref "U3")
      (value "MFS5600AMMA7ES")
      (footprint "MFS5600AMMA7ES")
      (description "Power Management, 36 V, 2 Step-Down DC-DC Converters, 2 Regulated Outputs, 32 Pins, HVQFN-EP")
      (fields (field (name "MANUFACTURER") "NXP Semiconductors"))
      (libsource (lib "Electronic Devices_LIB") (part "IC_REG_BUCK_MFS5600AMMA7ES"))
    )
  )
  (nets
    (net (code "2") (name "/3V3_5V0_PS_EN") (class "Default")
      (node (ref "U3") (pin "22") (pinfunction "EN2_22") (pintype "passive"))
    )
    (net (code "3") (name "/3V3_MON") (class "Default")
      (node (ref "R73") (pin "1") (pinfunction "1_1") (pintype "passive"))
      (node (ref "R76") (pin "2") (pinfunction "2_2") (pintype "passive"))
      (node (ref "U3") (pin "16") (pinfunction "NA_2_16") (pintype "passive"))
    )
    (net (code "4") (name "/5V0_MON") (class "Default")
      (node (ref "R74") (pin "1") (pinfunction "1_1") (pintype "passive"))
      (node (ref "R77") (pin "2") (pinfunction "2_2") (pintype "passive"))
      (node (ref "U3") (pin "15") (pinfunction "NA_1_15") (pintype "passive"))
    )
    (net (code "5") (name "/5V0_PS_ON") (class "Default")
      (node (ref "R79") (pin "1") (pinfunction "1_1") (pintype "passive"))
      (node (ref "U3") (pin "23") (pinfunction "EN1_23") (pintype "passive"))
    )
    (net (code "6") (name "/BIAS_IN") (class "Default")
      (node (ref "C171") (pin "2") (pinfunction "2_2") (pintype "passive"))
      (node (ref "R75") (pin "2") (pinfunction "2_2") (pintype "passive"))
      (node (ref "U3") (pin "29") (pinfunction "BIAS_IN_29") (pintype "passive"))
    )
    (net (code "7") (name "/FS0B") (class "Default")
      (node (ref "R71") (pin "1") (pinfunction "1_1") (pintype "passive"))
      (node (ref "U3") (pin "24") (pinfunction "NA_3_24") (pintype "passive"))
    )
    (net (code "8") (name "/FS_VCC") (class "Default")
      (node (ref "C170") (pin "2") (pinfunction "2_2") (pintype "passive"))
      (node (ref "U3") (pin "30") (pinfunction "VCC_30") (pintype "passive"))
    )
    (net (code "9") (name "/FUSE_12V") (class "Default")
      (node (ref "C150") (pin "1") (pinfunction "1_1") (pintype "passive"))
      (node (ref "D2") (pin "1") (pinfunction "K_1") (pintype "passive"))
      (node (ref "F1") (pin "2") (pinfunction "2_2") (pintype "passive"))
      (node (ref "FL1") (pin "1") (pinfunction "B_1") (pintype "passive"))
    )
    (net (code "10") (name "/I2C3_SCL") (class "Default")
      (node (ref "R68") (pin "1") (pinfunction "1_1") (pintype "passive"))
      (node (ref "U3") (pin "2") (pinfunction "SCL_2") (pintype "passive"))
    )
    (net (code "11") (name "/I2C3_SDA") (class "Default")
      (node (ref "R69") (pin "1") (pinfunction "1_1") (pintype "passive"))
      (node (ref "U3") (pin "3") (pinfunction "SDA_3") (pintype "passive"))
    )
    (net (code "12") (name "/IN_12V") (class "Default")
      (node (ref "F1") (pin "1") (pinfunction "1_1") (pintype "passive"))
      (node (ref "J7") (pin "2") (pinfunction "2_2") (pintype "passive"))
      (node (ref "J7") (pin "4") (pinfunction "4_4") (pintype "passive"))
      (node (ref "J8") (pin "1") (pinfunction "1_1") (pintype "passive"))
    )
    (net (code "13") (name "/PGOOD1") (class "Default")
      (node (ref "R67") (pin "1") (pinfunction "1_1") (pintype "passive"))
      (node (ref "U3") (pin "26") (pinfunction "PGOOD1_26") (pintype "passive"))
    )
    (net (code "14") (name "/PGOOD2") (class "Default")
      (node (ref "R66") (pin "1") (pinfunction "1_1") (pintype "passive"))
      (node (ref "U3") (pin "27") (pinfunction "PGOOD2_27") (pintype "passive"))
    )
    (net (code "15") (name "/SW2COMP") (class "Default")
      (node (ref "C182") (pin "2") (pinfunction "2_2") (pintype "passive"))
      (node (ref "R78") (pin "2") (pinfunction "2_2") (pintype "passive"))
      (node (ref "U3") (pin "5") (pinfunction "SW2COMP_5") (pintype "passive"))
    )
    (net (code "16") (name "/SW2GHS") (class "Default")
      (node (ref "Q2") (pin "2") (pinfunction "G1_2") (pintype "passive"))
      (node (ref "R65") (pin "1") (pinfunction "1_1") (pintype "passive"))
      (node (ref "U3") (pin "11") (pinfunction "SW2GHS_11") (pintype "passive"))
    )
    (net (code "17") (name "/SW2LX_2") (class "Default")
      (node (ref "C160") (pin "1") (pinfunction "1_1") (pintype "passive"))
      (node (ref "L11") (pin "1") (pinfunction "1_1") (pintype "passive"))
      (node (ref "Q2") (pin "1") (pinfunction "S1_1") (pintype "passive"))
      (node (ref "Q2") (pin "10") (pinfunction "D2_3_10") (pintype "passive"))
      (node (ref "Q2") (pin "5") (pinfunction "D2_1_5") (pintype "passive"))
      (node (ref "Q2") (pin "6") (pinfunction "D2_2_6") (pintype "passive"))
      (node (ref "R65") (pin "2") (pinfunction "2_2") (pintype "passive"))
      (node (ref "U3") (pin "10") (pinfunction "SW2LX_10") (pintype "passive"))
    )
    (net (code "18") (name "/SWCSN") (class "Default")
      (node (ref "R64") (pin "I2") (pinfunction "I2_I2") (pintype "passive"))
      (node (ref "U3") (pin "7") (pinfunction "SW2CSN_7") (pintype "passive"))
    )
    (net (code "19") (name "/SWCSP") (class "Default")
      (node (ref "Q2") (pin "4") (pinfunction "G2_4") (pintype "passive"))
      (node (ref "R64") (pin "E1") (pinfunction "E1_E1") (pintype "passive"))
      (node (ref "U3") (pin "8") (pinfunction "SW2CSP_8") (pintype "passive"))
      (node (ref "U3") (pin "9") (pinfunction "SW2GLS_9") (pintype "passive"))
    )
    (net (code "20") (name "/VDDOTP") (class "Default")
      (node (ref "R70") (pin "1") (pinfunction "1_1") (pintype "passive"))
      (node (ref "R72") (pin "2") (pinfunction "2_2") (pintype "passive"))
      (node (ref "TP38") (pin "1") (pinfunction "1_1") (pintype "passive"))
      (node (ref "U3") (pin "4") (pinfunction "GPIO1/VDDOTP_4") (pintype "passive"))
    )
    (net (code "21") (name "/VDIG") (class "Default")
      (node (ref "C172") (pin "2") (pinfunction "2_2") (pintype "passive"))
      (node (ref "U3") (pin "28") (pinfunction "VDIG_28") (pintype "passive"))
    )
    (net (code "23") (name "3V3_PS") (class "Default")
      (node (ref "C153") (pin "2") (pinfunction "2_2") (pintype "passive"))
      (node (ref "C154") (pin "2") (pinfunction "2_2") (pintype "passive"))
      (node (ref "C155") (pin "2") (pinfunction "2_2") (pintype "passive"))
      (node (ref "C156") (pin "2") (pinfunction "2_2") (pintype "passive"))
      (node (ref "C157") (pin "2") (pinfunction "2_2") (pintype "passive"))
      (node (ref "C158") (pin "2") (pinfunction "2_2") (pintype "passive"))
      (node (ref "R64") (pin "E2") (pinfunction "E2_E2") (pintype "passive"))
      (node (ref "R66") (pin "2") (pinfunction "2_2") (pintype "passive"))
      (node (ref "R67") (pin "2") (pinfunction "2_2") (pintype "passive"))
      (node (ref "R68") (pin "2") (pinfunction "2_2") (pintype "passive"))
      (node (ref "R69") (pin "2") (pinfunction "2_2") (pintype "passive"))
      (node (ref "R70") (pin "2") (pinfunction "2_2") (pintype "passive"))
      (node (ref "R71") (pin "2") (pinfunction "2_2") (pintype "passive"))
      (node (ref "R73") (pin "2") (pinfunction "2_2") (pintype "passive"))
      (node (ref "TP36") (pin "1") (pinfunction "1_1") (pintype "passive"))
      (node (ref "U3") (pin "1") (pinfunction "VDDIO_1") (pintype "passive"))
      (node (ref "U3") (pin "6") (pinfunction "SW2FB_6") (pintype "passive"))
    )
    (net (code "24") (name "5V0_PS") (class "Default")
      (node (ref "C161") (pin "2") (pinfunction "2_2") (pintype "passive"))
      (node (ref "C162") (pin "2") (pinfunction "2_2") (pintype "passive"))
      (node (ref "C163") (pin "2") (pinfunction "2_2") (pintype "passive"))
      (node (ref "C164") (pin "2") (pinfunction "2_2") (pintype "passive"))
      (node (ref "C165") (pin "2") (pinfunction "2_2") (pintype "passive"))
      (node (ref "C166") (pin "2") (pinfunction "2_2") (pintype "passive"))
      (node (ref "C167") (pin "2") (pinfunction "2_2") (pintype "passive"))
      (node (ref "C168") (pin "2") (pinfunction "2_2") (pintype "passive"))
      (node (ref "C173") (pin "2") (pinfunction "2_2") (pintype "passive"))
      (node (ref "C174") (pin "2") (pinfunction "2_2") (pintype "passive"))
      (node (ref "C175") (pin "2") (pinfunction "2_2") (pintype "passive"))
      (node (ref "C176") (pin "2") (pinfunction "2_2") (pintype "passive"))
      (node (ref "C177") (pin "2") (pinfunction "2_2") (pintype "passive"))
      (node (ref "C178") (pin "2") (pinfunction "2_2") (pintype "passive"))
      (node (ref "C179") (pin "2") (pinfunction "2_2") (pintype "passive"))
      (node (ref "C180") (pin "2") (pinfunction "2_2") (pintype "passive"))
      (node (ref "C181") (pin "2") (pinfunction "2_2") (pintype "passive"))
      (node (ref "L12") (pin "2") (pinfunction "2_2") (pintype "passive"))
      (node (ref "R74") (pin "2") (pinfunction "2_2") (pintype "passive"))
      (node (ref "R75") (pin "1") (pinfunction "1_1") (pintype "passive"))
      (node (ref "TP37") (pin "1") (pinfunction "1_1") (pintype "passive"))
      (node (ref "U3") (pin "25") (pinfunction "SW1FB_25") (pintype "passive"))
    )
    (net (code "25") (name "12V0") (class "Default")
      (node (ref "C149") (pin "2") (pinfunction "2_2") (pintype "passive"))
      (node (ref "C152") (pin "2") (pinfunction "2_2") (pintype "passive"))
      (node (ref "C159") (pin "2") (pinfunction "2_2") (pintype "passive"))
      (node (ref "Q2") (pin "7") (pinfunction "D1_1_7") (pintype "passive"))
      (node (ref "Q2") (pin "8") (pinfunction "D1_2_8") (pintype "passive"))
      (node (ref "Q2") (pin "9") (pinfunction "D1_3_9") (pintype "passive"))
      (node (ref "R63") (pin "2") (pinfunction "2_2") (pintype "passive"))
      (node (ref "TP35") (pin "1") (pinfunction "1_1") (pintype "passive"))
      (node (ref "U3") (pin "18") (pinfunction "SW1IN_1_18") (pintype "passive"))
      (node (ref "U3") (pin "19") (pinfunction "SW1IN_2_19") (pintype "passive"))
      (node (ref "U3") (pin "32") (pinfunction "VIN_32") (pintype "passive"))
    )
    (net (code "26") (name "FLT_12V") (class "Default")
      (node (ref "C151") (pin "1") (pinfunction "1_1") (pintype "passive"))
      (node (ref "FL1") (pin "2") (pinfunction "CB_2") (pintype "passive"))
      (node (ref "R63") (pin "1") (pinfunction "1_1") (pintype "passive"))
      (node (ref "TP34") (pin "1") (pinfunction "1_1") (pintype "passive"))
    )
    (net (code "27") (name "GND") (class "Default")
      (node (ref "C149") (pin "1") (pinfunction "1_1") (pintype "passive"))
      (node (ref "C150") (pin "2") (pinfunction "2_2") (pintype "passive"))
      (node (ref "C151") (pin "2") (pinfunction "2_2") (pintype "passive"))
      (node (ref "C152") (pin "1") (pinfunction "1_1") (pintype "passive"))
      (node (ref "C153") (pin "1") (pinfunction "1_1") (pintype "passive"))
      (node (ref "C154") (pin "1") (pinfunction "1_1") (pintype "passive"))
      (node (ref "C155") (pin "1") (pinfunction "1_1") (pintype "passive"))
      (node (ref "C156") (pin "1") (pinfunction "1_1") (pintype "passive"))
      (node (ref "C157") (pin "1") (pinfunction "1_1") (pintype "passive"))
      (node (ref "C158") (pin "1") (pinfunction "1_1") (pintype "passive"))
      (node (ref "C159") (pin "1") (pinfunction "1_1") (pintype "passive"))
      (node (ref "C161") (pin "1") (pinfunction "1_1") (pintype "passive"))
      (node (ref "C162") (pin "1") (pinfunction "1_1") (pintype "passive"))
      (node (ref "C163") (pin "1") (pinfunction "1_1") (pintype "passive"))
      (node (ref "C164") (pin "1") (pinfunction "1_1") (pintype "passive"))
      (node (ref "C165") (pin "1") (pinfunction "1_1") (pintype "passive"))
      (node (ref "C166") (pin "1") (pinfunction "1_1") (pintype "passive"))
      (node (ref "C167") (pin "1") (pinfunction "1_1") (pintype "passive"))
      (node (ref "C168") (pin "1") (pinfunction "1_1") (pintype "passive"))
      (node (ref "C170") (pin "1") (pinfunction "1_1") (pintype "passive"))
      (node (ref "C171") (pin "1") (pinfunction "1_1") (pintype "passive"))
      (node (ref "C172") (pin "1") (pinfunction "1_1") (pintype "passive"))
      (node (ref "C173") (pin "1") (pinfunction "1_1") (pintype "passive"))
      (node (ref "C174") (pin "1") (pinfunction "1_1") (pintype "passive"))
      (node (ref "C175") (pin "1") (pinfunction "1_1") (pintype "passive"))
      (node (ref "C176") (pin "1") (pinfunction "1_1") (pintype "passive"))
      (node (ref "C177") (pin "1") (pinfunction "1_1") (pintype "passive"))
      (node (ref "C178") (pin "1") (pinfunction "1_1") (pintype "passive"))
      (node (ref "C179") (pin "1") (pinfunction "1_1") (pintype "passive"))
      (node (ref "C180") (pin "1") (pinfunction "1_1") (pintype "passive"))
      (node (ref "C181") (pin "1") (pinfunction "1_1") (pintype "passive"))
      (node (ref "C182") (pin "1") (pinfunction "1_1") (pintype "passive"))
      (node (ref "C183") (pin "1") (pinfunction "1_1") (pintype "passive"))
      (node (ref "D2") (pin "2") (pinfunction "A_2") (pintype "passive"))
      (node (ref "FL1") (pin "3") (pinfunction "PSG_3") (pintype "passive"))
      (node (ref "FL1") (pin "4") (pinfunction "CG_4") (pintype "passive"))
      (node (ref "FL1") (pin "5") (pinfunction "CG_5") (pintype "passive"))
      (node (ref "FL1") (pin "6") (pinfunction "CG_6") (pintype "passive"))
      (node (ref "J7") (pin "1") (pinfunction "1_1") (pintype "passive"))
      (node (ref "J7") (pin "3") (pinfunction "3_3") (pintype "passive"))
      (node (ref "J7") (pin "S1") (pinfunction "SHIELD_S1") (pintype "passive"))
      (node (ref "J7") (pin "S2") (pinfunction "SHIELD_S2") (pintype "passive"))
      (node (ref "J7") (pin "S3") (pinfunction "SHIELD_S3") (pintype "passive"))
      (node (ref "J8") (pin "2") (pinfunction "2_2") (pintype "passive"))
      (node (ref "Q2") (pin "3") (pinfunction "S2_3") (pintype "passive"))
      (node (ref "R72") (pin "1") (pinfunction "1_1") (pintype "passive"))
      (node (ref "R76") (pin "1") (pinfunction "1_1") (pintype "passive"))
      (node (ref "R77") (pin "1") (pinfunction "1_1") (pintype "passive"))
      (node (ref "R79") (pin "2") (pinfunction "2_2") (pintype "passive"))
      (node (ref "U3") (pin "13") (pinfunction "GPO3_13") (pintype "passive"))
      (node (ref "U3") (pin "14") (pinfunction "GPO2_14") (pintype "passive"))
      (node (ref "U3") (pin "31") (pinfunction "MODE/SYNCIN_31") (pintype "passive"))
      (node (ref "U3") (pin "33") (pinfunction "GND_33") (pintype "passive"))
      (node (ref "U3") (pin "34") (pinfunction "EP_1_34") (pintype "passive"))
      (node (ref "U3") (pin "35") (pinfunction "EP_2_35") (pintype "passive"))
      (node (ref "U3") (pin "36") (pinfunction "EP_3_36") (pintype "passive"))
      (node (ref "U3") (pin "37") (pinfunction "EP_4_37") (pintype "passive"))
    )
    (net (code "28") (name "Net-(C183-Pad2)") (class "Default")
      (node (ref "C183") (pin "2") (pinfunction "2_2") (pintype "passive"))
      (node (ref "R78") (pin "1") (pinfunction "1_1") (pintype "passive"))
    )
    (net (code "29") (name "Net-(L11-Pad2)") (class "Default")
      (node (ref "L11") (pin "2") (pinfunction "2_2") (pintype "passive"))
      (node (ref "R64") (pin "I1") (pinfunction "I1_I1") (pintype "passive"))
    )
    (net (code "30") (name "Net-(U3-SW1BOOT)") (class "Default")
      (node (ref "C169") (pin "1") (pinfunction "1_1") (pintype "passive"))
      (node (ref "U3") (pin "17") (pinfunction "SW1BOOT_17") (pintype "passive"))
    )
    (net (code "31") (name "Net-(U3-SW1LX_1)") (class "Default")
      (node (ref "C169") (pin "2") (pinfunction "2_2") (pintype "passive"))
      (node (ref "L12") (pin "1") (pinfunction "1_1") (pintype "passive"))
      (node (ref "U3") (pin "20") (pinfunction "SW1LX_1_20") (pintype "passive"))
      (node (ref "U3") (pin "21") (pinfunction "SW1LX_2_21") (pintype "passive"))
    )
    (net (code "32") (name "Net-(U3-SW2BO_OT)") (class "Default")
      (node (ref "C160") (pin "2") (pinfunction "2_2") (pintype "passive"))
      (node (ref "U3") (pin "12") (pinfunction "SW2BO_OT_12") (pintype "passive"))
    )
  )
)
